# MinieasyMySens-V02-Build008.net
KiCad netlist of a schematic drawn in EAGLE
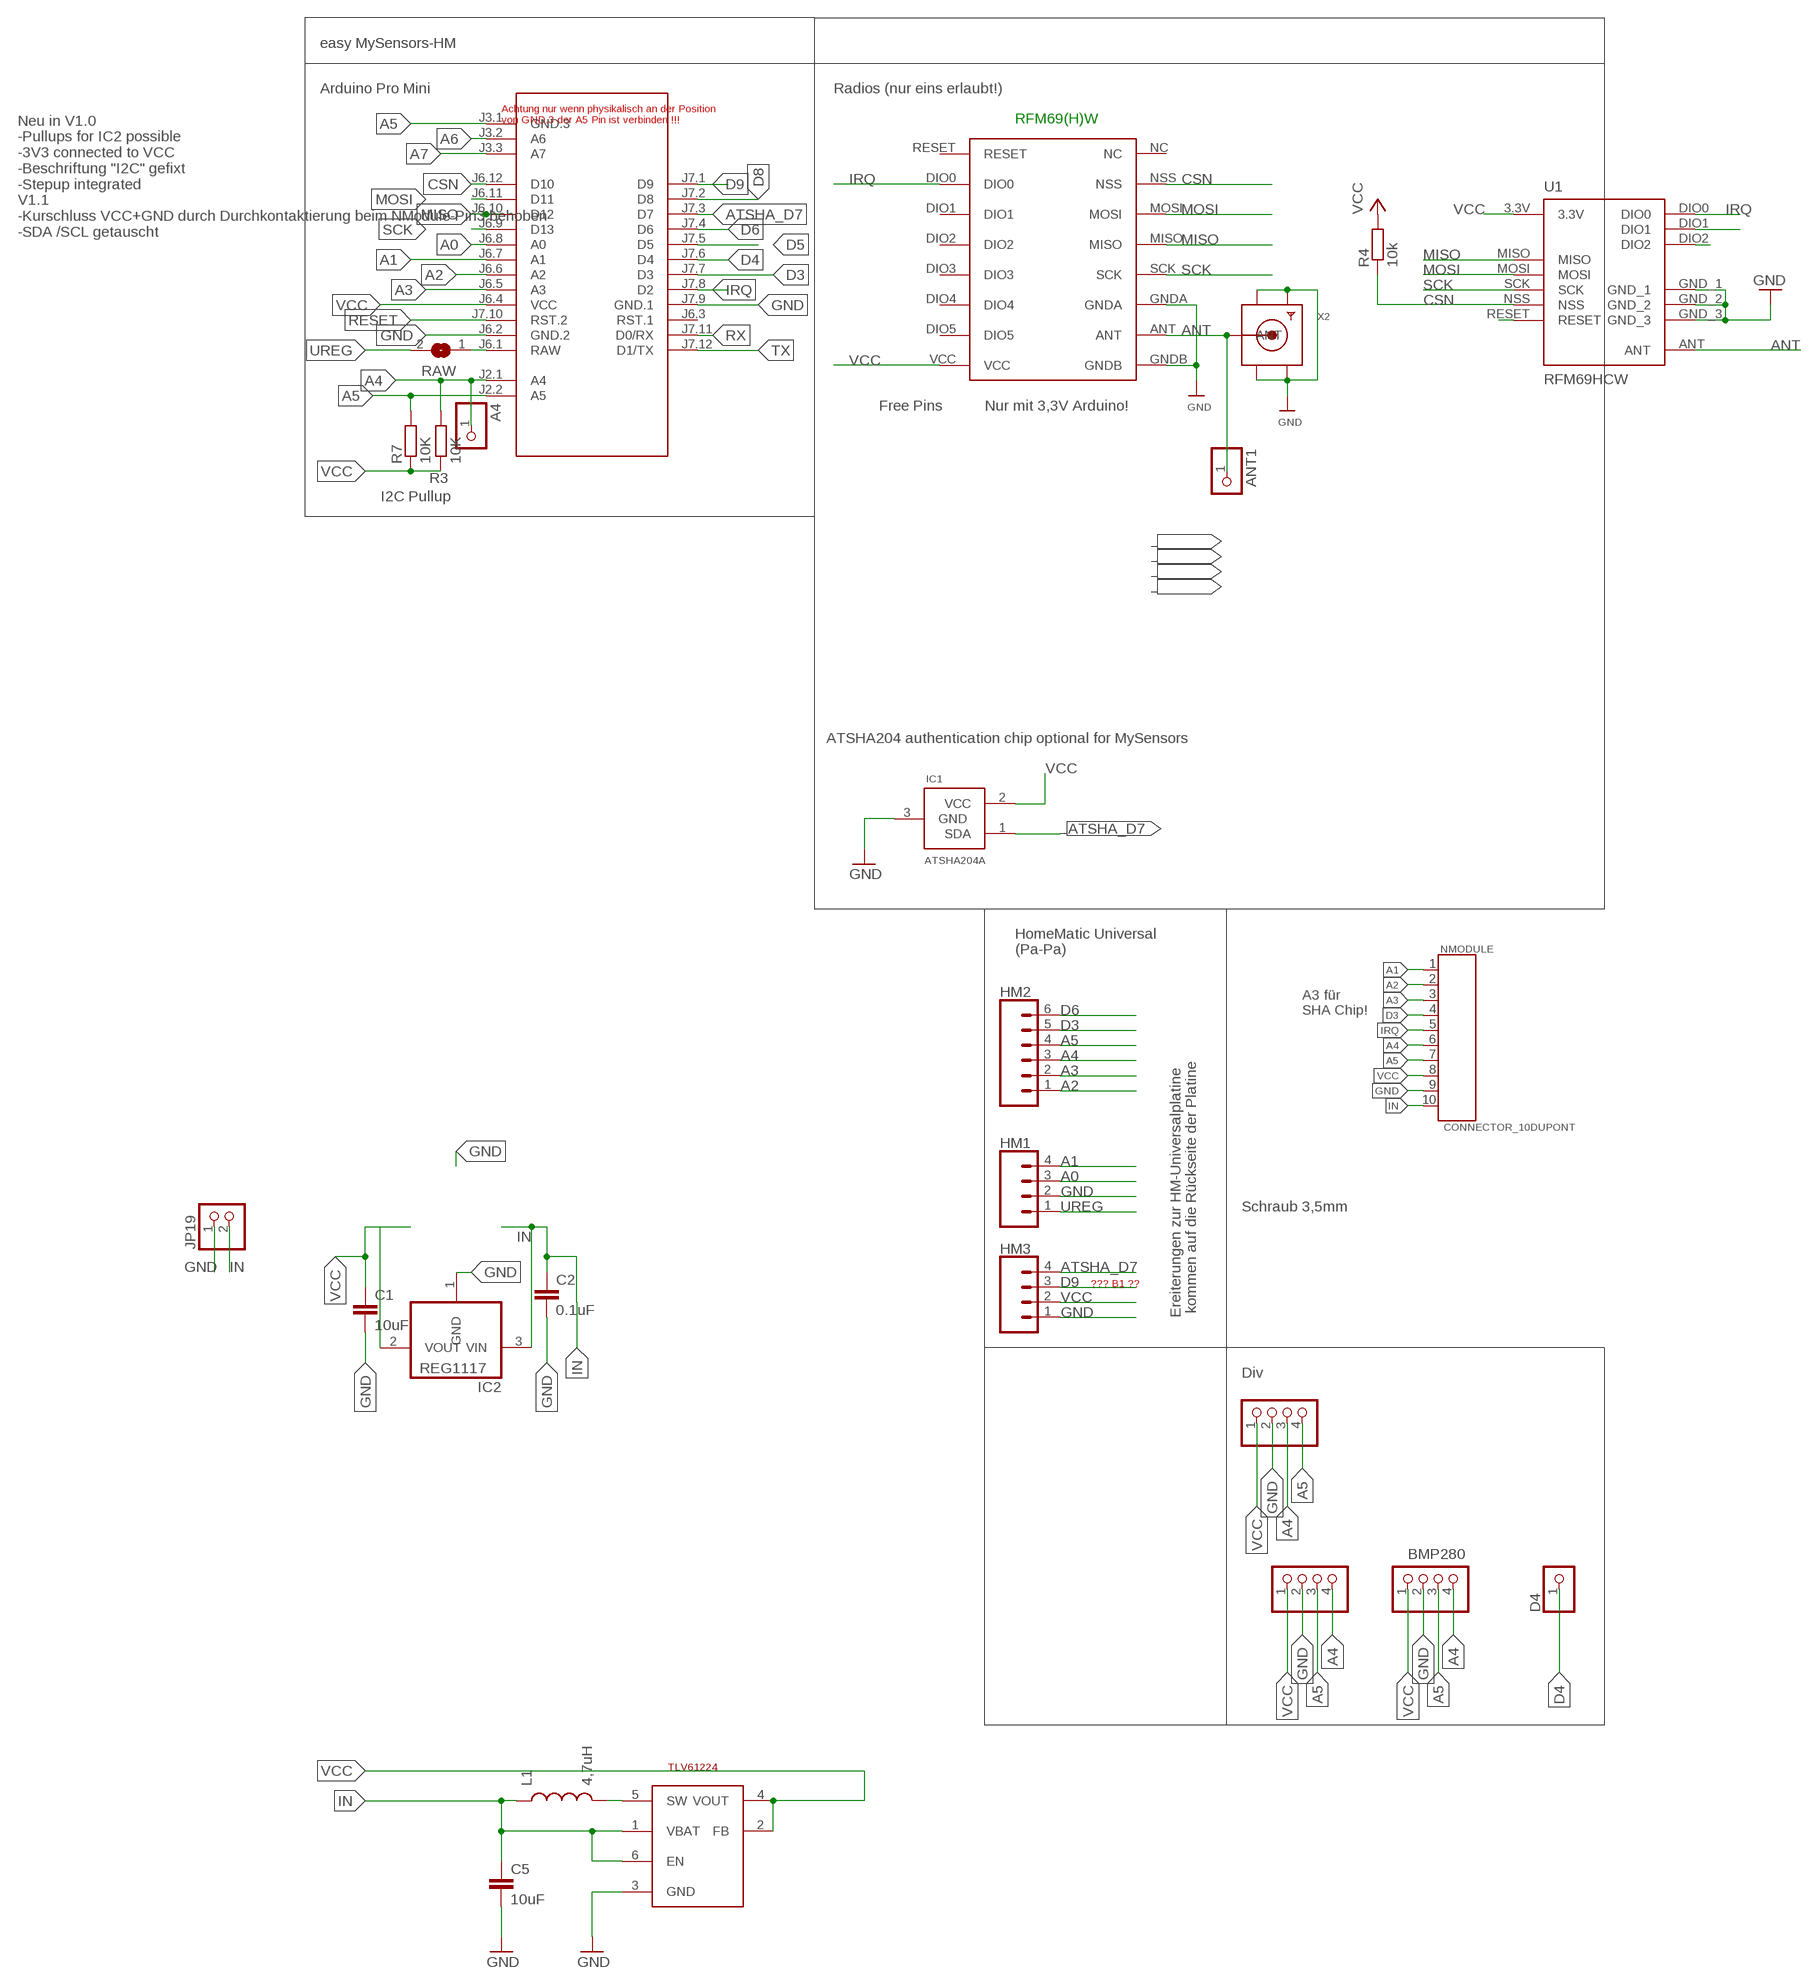
[diagram p0: schematic, sheet 1]

(export (version "E")
  (design (tool "Eeschema 10.0.6"))
  (components
    (comp (ref "A4")
      (value "PINHD-1X1")
      (footprint "eagle-import:1X01")
      (libsource (lib "eagle-import") (part "PINHD-1X1"))
    )
    (comp (ref "ANT1")
      (value "PINHD-1X1")
      (footprint "eagle-import:1X01")
      (libsource (lib "eagle-import") (part "PINHD-1X1"))
    )
    (comp (ref "BH1750")
      (value "PINHD-1X04_2.54-S")
      (footprint "eagle-import:1X04-S")
      (libsource (lib "eagle-import") (part "PINHD-1X04_2.54-S"))
    )
    (comp (ref "C1")
      (value "10uF")
      (footprint "eagle-import:C1210")
      (libsource (lib "eagle-import") (part "C-EUC1210"))
    )
    (comp (ref "C2")
      (value "0.1uF")
      (footprint "eagle-import:C1206")
      (libsource (lib "eagle-import") (part "C-EUC1206"))
    )
    (comp (ref "C5")
      (value "10uF")
      (footprint "eagle-import:0805")
      (libsource (lib "eagle-import") (part "CAP0805"))
    )
    (comp (ref "D4")
      (value "PINHD-1X1")
      (footprint "eagle-import:1X01")
      (libsource (lib "eagle-import") (part "PINHD-1X1"))
    )
    (comp (ref "HM1")
      (value "CONN_04")
      (footprint "eagle-import:1X04")
      (libsource (lib "eagle-import") (part "CONN_04"))
    )
    (comp (ref "HM2")
      (value "CONN_06SILK_FEMALE_PTH")
      (footprint "eagle-import:1X06")
      (libsource (lib "eagle-import") (part "CONN_06SILK_FEMALE_PTH"))
    )
    (comp (ref "HM3")
      (value "CONN_04")
      (footprint "eagle-import:1X04")
      (libsource (lib "eagle-import") (part "CONN_04"))
    )
    (comp (ref "I2C-1")
      (value "PINHD-1X04_2.54-S")
      (footprint "eagle-import:1X04-S")
      (libsource (lib "eagle-import") (part "PINHD-1X04_2.54-S"))
    )
    (comp (ref "I2C-2")
      (value "PINHD-1X04_2.54-S")
      (footprint "eagle-import:1X04-S")
      (libsource (lib "eagle-import") (part "PINHD-1X04_2.54-S"))
    )
    (comp (ref "IC1")
      (value "ATSHA204A")
      (footprint "eagle-import:SOT23")
      (libsource (lib "eagle-import") (part "ATSHA204A"))
    )
    (comp (ref "IC2")
      (value "REG1117")
      (footprint "eagle-import:SOT223")
      (libsource (lib "eagle-import") (part "REG1117"))
    )
    (comp (ref "JP19")
      (value "PINHD-1X2")
      (footprint "eagle-import:1X02")
      (libsource (lib "eagle-import") (part "PINHD-1X2"))
    )
    (comp (ref "L1")
      (value "4,7uH")
      (footprint "eagle-import:0805")
      (libsource (lib "eagle-import") (part "INDUCTOR0805"))
    )
    (comp (ref "M1")
      (value "ARDUINO-PRO-MINI-3.3V#NP")
      (footprint "eagle-import:ARDUINO-PRO-MINI#NP")
      (libsource (lib "eagle-import") (part "ARDUINO-PRO-MINI-#NP3.3V"))
    )
    (comp (ref "NMODULE")
      (value "CONNECTOR_10DUPONT")
      (footprint "eagle-import:DUPONT_10")
      (libsource (lib "eagle-import") (part "CONNECTOR_10DUPONT"))
    )
    (comp (ref "R3")
      (value "10K")
      (footprint "eagle-import:R0805")
      (libsource (lib "eagle-import") (part "R-EU_R0805"))
    )
    (comp (ref "R4")
      (value "10k")
      (footprint "eagle-import:M0805")
      (libsource (lib "eagle-import") (part "R-EU_M0805"))
    )
    (comp (ref "R7")
      (value "10K")
      (footprint "eagle-import:R0805")
      (libsource (lib "eagle-import") (part "R-EU_R0805"))
    )
    (comp (ref "RAW") (value "SJ") (footprint "eagle-import:SJ") (libsource (lib "eagle-import") (part "SJ")))
    (comp (ref "RFM69W")
      (value "RFM69HW")
      (footprint "eagle-import:RFM")
      (libsource (lib "eagle-import") (part "RFM69HW"))
    )
    (comp (ref "STEPUP")
      (value "TLV61224")
      (footprint "eagle-import:SOT23-6L")
      (libsource (lib "eagle-import") (part "TI-TLV61224"))
    )
    (comp (ref "U1")
      (value "RFM69HCW")
      (footprint "eagle-import:RFM69HCW-XXXS2")
      (libsource (lib "eagle-import") (part "RFM69HCW"))
    )
    (comp (ref "X2")
      (value "SMACONNECTOR_EDGE")
      (footprint "eagle-import:SMA_EDGELAUNCH")
      (libsource (lib "eagle-import") (part "SMACONNECTOR_EDGE"))
    )
  )
  (nets
    (net (code "1") (name "/ANT") (class "Default")
      (node (ref "ANT1") (pin "1") (pinfunction "1_1") (pintype "passive"))
      (node (ref "RFM69W") (pin "ANT") (pinfunction "ANT_ANT") (pintype "bidirectional"))
      (node (ref "U1") (pin "ANT") (pinfunction "ANT_ANT") (pintype "passive"))
      (node (ref "X2") (pin "P") (pinfunction "ANT_P") (pintype "bidirectional"))
    )
    (net (code "2") (name "A0") (class "Default")
      (node (ref "HM1") (pin "3") (pinfunction "3_3") (pintype "passive"))
      (node (ref "M1") (pin "J6.8") (pinfunction "A0_J6.8") (pintype "bidirectional"))
    )
    (net (code "3") (name "A1") (class "Default")
      (node (ref "HM1") (pin "4") (pinfunction "4_4") (pintype "passive"))
      (node (ref "M1") (pin "J6.7") (pinfunction "A1_J6.7") (pintype "bidirectional"))
      (node (ref "NMODULE") (pin "1") (pinfunction "1_1") (pintype "bidirectional"))
    )
    (net (code "4") (name "A2") (class "Default")
      (node (ref "HM2") (pin "1") (pinfunction "1_1") (pintype "passive"))
      (node (ref "M1") (pin "J6.6") (pinfunction "A2_J6.6") (pintype "bidirectional"))
      (node (ref "NMODULE") (pin "2") (pinfunction "2_2") (pintype "bidirectional"))
    )
    (net (code "5") (name "A3") (class "Default")
      (node (ref "HM2") (pin "2") (pinfunction "2_2") (pintype "passive"))
      (node (ref "M1") (pin "J6.5") (pinfunction "A3_J6.5") (pintype "bidirectional"))
      (node (ref "NMODULE") (pin "3") (pinfunction "3_3") (pintype "bidirectional"))
    )
    (net (code "6") (name "A4") (class "Default")
      (node (ref "A4") (pin "1") (pinfunction "1_1") (pintype "passive"))
      (node (ref "BH1750") (pin "4") (pinfunction "4_4") (pintype "passive"))
      (node (ref "HM2") (pin "3") (pinfunction "3_3") (pintype "passive"))
      (node (ref "I2C-1") (pin "4") (pinfunction "4_4") (pintype "passive"))
      (node (ref "I2C-2") (pin "3") (pinfunction "3_3") (pintype "passive"))
      (node (ref "M1") (pin "J2.1") (pinfunction "A4_J2.1") (pintype "bidirectional"))
      (node (ref "NMODULE") (pin "6") (pinfunction "6_6") (pintype "bidirectional"))
      (node (ref "R3") (pin "2") (pinfunction "2_2") (pintype "passive"))
    )
    (net (code "7") (name "A5") (class "Default")
      (node (ref "BH1750") (pin "3") (pinfunction "3_3") (pintype "passive"))
      (node (ref "HM2") (pin "4") (pinfunction "4_4") (pintype "passive"))
      (node (ref "I2C-1") (pin "3") (pinfunction "3_3") (pintype "passive"))
      (node (ref "I2C-2") (pin "4") (pinfunction "4_4") (pintype "passive"))
      (node (ref "M1") (pin "J2.2") (pinfunction "A5_J2.2") (pintype "bidirectional"))
      (node (ref "M1") (pin "J3.1") (pinfunction "GND.3_J3.1") (pintype "bidirectional"))
      (node (ref "NMODULE") (pin "7") (pinfunction "7_7") (pintype "bidirectional"))
      (node (ref "R7") (pin "2") (pinfunction "2_2") (pintype "passive"))
    )
    (net (code "8") (name "A6") (class "Default")
      (node (ref "M1") (pin "J3.2") (pinfunction "A6_J3.2") (pintype "bidirectional"))
    )
    (net (code "9") (name "A7") (class "Default")
      (node (ref "M1") (pin "J3.3") (pinfunction "A7_J3.3") (pintype "bidirectional"))
    )
    (net (code "10") (name "ATSHA_D7") (class "Default")
      (node (ref "HM3") (pin "4") (pinfunction "4_4") (pintype "passive"))
      (node (ref "IC1") (pin "1") (pinfunction "SDA_1") (pintype "bidirectional"))
      (node (ref "M1") (pin "J7.3") (pinfunction "D7_J7.3") (pintype "bidirectional"))
    )
    (net (code "11") (name "CSN") (class "Default")
      (node (ref "M1") (pin "J6.12") (pinfunction "D10_J6.12") (pintype "bidirectional"))
      (node (ref "R4") (pin "1") (pinfunction "1_1") (pintype "passive"))
      (node (ref "RFM69W") (pin "NSS") (pinfunction "NSS_NSS") (pintype "bidirectional"))
      (node (ref "U1") (pin "NSS") (pinfunction "NSS_NSS") (pintype "input"))
    )
    (net (code "12") (name "D3") (class "Default")
      (node (ref "HM2") (pin "5") (pinfunction "5_5") (pintype "passive"))
      (node (ref "M1") (pin "J7.7") (pinfunction "D3_J7.7") (pintype "bidirectional"))
      (node (ref "NMODULE") (pin "4") (pinfunction "4_4") (pintype "bidirectional"))
    )
    (net (code "13") (name "D4") (class "Default")
      (node (ref "D4") (pin "1") (pinfunction "1_1") (pintype "passive"))
      (node (ref "M1") (pin "J7.6") (pinfunction "D4_J7.6") (pintype "bidirectional"))
    )
    (net (code "14") (name "D5") (class "Default")
      (node (ref "M1") (pin "J7.5") (pinfunction "D5_J7.5") (pintype "bidirectional"))
    )
    (net (code "15") (name "D6") (class "Default")
      (node (ref "HM2") (pin "6") (pinfunction "6_6") (pintype "passive"))
      (node (ref "M1") (pin "J7.4") (pinfunction "D6_J7.4") (pintype "bidirectional"))
    )
    (net (code "16") (name "D8") (class "Default")
      (node (ref "M1") (pin "J7.2") (pinfunction "D8_J7.2") (pintype "bidirectional"))
    )
    (net (code "17") (name "D9") (class "Default")
      (node (ref "HM3") (pin "3") (pinfunction "3_3") (pintype "passive"))
      (node (ref "M1") (pin "J7.1") (pinfunction "D9_J7.1") (pintype "bidirectional"))
    )
    (net (code "18") (name "GND") (class "Default")
      (node (ref "BH1750") (pin "2") (pinfunction "2_2") (pintype "passive"))
      (node (ref "C1") (pin "2") (pinfunction "2_2") (pintype "passive"))
      (node (ref "C2") (pin "2") (pinfunction "2_2") (pintype "passive"))
      (node (ref "C5") (pin "2") (pinfunction "2_2") (pintype "passive"))
      (node (ref "HM1") (pin "2") (pinfunction "2_2") (pintype "passive"))
      (node (ref "HM3") (pin "1") (pinfunction "1_1") (pintype "passive"))
      (node (ref "I2C-1") (pin "2") (pinfunction "2_2") (pintype "passive"))
      (node (ref "I2C-2") (pin "2") (pinfunction "2_2") (pintype "passive"))
      (node (ref "IC1") (pin "3") (pinfunction "GND_3") (pintype "bidirectional"))
      (node (ref "IC2") (pin "1") (pinfunction "GND_1") (pintype "power_in"))
      (node (ref "JP19") (pin "1") (pinfunction "1_1") (pintype "passive"))
      (node (ref "M1") (pin "J6.2") (pinfunction "GND.2_J6.2") (pintype "power_in"))
      (node (ref "M1") (pin "J7.9") (pinfunction "GND.1_J7.9") (pintype "power_in"))
      (node (ref "NMODULE") (pin "9") (pinfunction "9_9") (pintype "bidirectional"))
      (node (ref "RFM69W") (pin "GNDA") (pinfunction "GNDA_GNDA") (pintype "bidirectional"))
      (node (ref "RFM69W") (pin "GNDB") (pinfunction "GNDB_GNDB") (pintype "bidirectional"))
      (node (ref "STEPUP") (pin "3") (pinfunction "GND_3") (pintype "power_in"))
      (node (ref "U1") (pin "GND_1") (pinfunction "GND_1_GND_1") (pintype "power_in"))
      (node (ref "U1") (pin "GND_2") (pinfunction "GND_2_GND_2") (pintype "power_in"))
      (node (ref "U1") (pin "GND_3") (pinfunction "GND_3_GND_3") (pintype "power_in"))
      (node (ref "X2") (pin "GND@1") (pinfunction "GND4_GND@1") (pintype "power_in"))
      (node (ref "X2") (pin "GND@2") (pinfunction "GND3_GND@2") (pintype "power_in"))
      (node (ref "X2") (pin "GND@3") (pinfunction "GND2_GND@3") (pintype "power_in"))
      (node (ref "X2") (pin "GND@4") (pinfunction "GND1_GND@4") (pintype "power_in"))
    )
    (net (code "19") (name "IN") (class "Default")
      (node (ref "C2") (pin "1") (pinfunction "1_1") (pintype "passive"))
      (node (ref "C5") (pin "1") (pinfunction "1_1") (pintype "passive"))
      (node (ref "IC2") (pin "3") (pinfunction "VIN_3") (pintype "input"))
      (node (ref "JP19") (pin "2") (pinfunction "2_2") (pintype "passive"))
      (node (ref "L1") (pin "1") (pinfunction "1_1") (pintype "passive"))
      (node (ref "NMODULE") (pin "10") (pinfunction "10_10") (pintype "bidirectional"))
      (node (ref "STEPUP") (pin "1") (pinfunction "VBAT_1") (pintype "power_in"))
      (node (ref "STEPUP") (pin "6") (pinfunction "EN_6") (pintype "input"))
    )
    (net (code "20") (name "IRQ") (class "Default")
      (node (ref "M1") (pin "J7.8") (pinfunction "D2_J7.8") (pintype "bidirectional"))
      (node (ref "NMODULE") (pin "5") (pinfunction "5_5") (pintype "bidirectional"))
      (node (ref "RFM69W") (pin "DIO0") (pinfunction "DIO0_DIO0") (pintype "bidirectional"))
      (node (ref "U1") (pin "DIO0") (pinfunction "DIO0_DIO0") (pintype "bidirectional"))
    )
    (net (code "21") (name "MISO") (class "Default")
      (node (ref "M1") (pin "J6.10") (pinfunction "D12_J6.10") (pintype "bidirectional"))
      (node (ref "RFM69W") (pin "MISO") (pinfunction "MISO_MISO") (pintype "bidirectional"))
      (node (ref "U1") (pin "MISO") (pinfunction "MISO_MISO") (pintype "bidirectional"))
    )
    (net (code "22") (name "MOSI") (class "Default")
      (node (ref "M1") (pin "J6.11") (pinfunction "D11_J6.11") (pintype "bidirectional"))
      (node (ref "RFM69W") (pin "MOSI") (pinfunction "MOSI_MOSI") (pintype "bidirectional"))
      (node (ref "U1") (pin "MOSI") (pinfunction "MOSI_MOSI") (pintype "input"))
    )
    (net (code "23") (name "Net-(M1-RAW)") (class "Default")
      (node (ref "M1") (pin "J6.1") (pinfunction "RAW_J6.1") (pintype "power_in"))
      (node (ref "RAW") (pin "1") (pinfunction "1_1") (pintype "passive"))
    )
    (net (code "24") (name "Net-(STEPUP-SW)") (class "Default")
      (node (ref "L1") (pin "2") (pinfunction "2_2") (pintype "passive"))
      (node (ref "STEPUP") (pin "5") (pinfunction "SW_5") (pintype "power_in"))
    )
    (net (code "25") (name "RESET") (class "Default")
      (node (ref "M1") (pin "J7.10") (pinfunction "RST.2_J7.10") (pintype "bidirectional"))
    )
    (net (code "26") (name "RX") (class "Default")
      (node (ref "M1") (pin "J7.11") (pinfunction "D0/RX_J7.11") (pintype "bidirectional"))
    )
    (net (code "27") (name "SCK") (class "Default")
      (node (ref "M1") (pin "J6.9") (pinfunction "D13_J6.9") (pintype "bidirectional"))
      (node (ref "RFM69W") (pin "SCK") (pinfunction "SCK_SCK") (pintype "bidirectional"))
      (node (ref "U1") (pin "SCK") (pinfunction "SCK_SCK") (pintype "input"))
    )
    (net (code "28") (name "TX") (class "Default")
      (node (ref "M1") (pin "J7.12") (pinfunction "D1/TX_J7.12") (pintype "bidirectional"))
    )
    (net (code "29") (name "UREG") (class "Default")
      (node (ref "HM1") (pin "1") (pinfunction "1_1") (pintype "passive"))
      (node (ref "RAW") (pin "2") (pinfunction "2_2") (pintype "passive"))
    )
    (net (code "30") (name "VCC") (class "Default")
      (node (ref "BH1750") (pin "1") (pinfunction "1_1") (pintype "passive"))
      (node (ref "C1") (pin "1") (pinfunction "1_1") (pintype "passive"))
      (node (ref "HM3") (pin "2") (pinfunction "2_2") (pintype "passive"))
      (node (ref "I2C-1") (pin "1") (pinfunction "1_1") (pintype "passive"))
      (node (ref "I2C-2") (pin "1") (pinfunction "1_1") (pintype "passive"))
      (node (ref "IC1") (pin "2") (pinfunction "VCC_2") (pintype "bidirectional"))
      (node (ref "IC2") (pin "2") (pinfunction "VOUT_2") (pintype "output"))
      (node (ref "M1") (pin "J6.4") (pinfunction "VCC_J6.4") (pintype "power_in"))
      (node (ref "NMODULE") (pin "8") (pinfunction "8_8") (pintype "bidirectional"))
      (node (ref "R3") (pin "1") (pinfunction "1_1") (pintype "passive"))
      (node (ref "R4") (pin "2") (pinfunction "2_2") (pintype "passive"))
      (node (ref "R7") (pin "1") (pinfunction "1_1") (pintype "passive"))
      (node (ref "RFM69W") (pin "VCC") (pinfunction "VCC_VCC") (pintype "bidirectional"))
      (node (ref "STEPUP") (pin "2") (pinfunction "FB_2") (pintype "input"))
      (node (ref "STEPUP") (pin "4") (pinfunction "VOUT_4") (pintype "power_in"))
      (node (ref "U1") (pin "3.3V") (pinfunction "3.3V_3.3V") (pintype "power_in"))
    )
    (net (code "31") (name "unconnected-(M1-RST.1-PadJ6.3)") (class "Default")
      (node (ref "M1") (pin "J6.3") (pinfunction "RST.1_J6.3") (pintype "bidirectional"))
    )
    (net (code "32") (name "unconnected-(RFM69W-PadDIO1)") (class "Default")
      (node (ref "RFM69W") (pin "DIO1") (pinfunction "DIO1_DIO1") (pintype "bidirectional"))
    )
    (net (code "33") (name "unconnected-(RFM69W-PadDIO2)") (class "Default")
      (node (ref "RFM69W") (pin "DIO2") (pinfunction "DIO2_DIO2") (pintype "bidirectional"))
    )
    (net (code "34") (name "unconnected-(RFM69W-PadDIO3)") (class "Default")
      (node (ref "RFM69W") (pin "DIO3") (pinfunction "DIO3_DIO3") (pintype "bidirectional"))
    )
    (net (code "35") (name "unconnected-(RFM69W-PadDIO4)") (class "Default")
      (node (ref "RFM69W") (pin "DIO4") (pinfunction "DIO4_DIO4") (pintype "bidirectional"))
    )
    (net (code "36") (name "unconnected-(RFM69W-PadDIO5)") (class "Default")
      (node (ref "RFM69W") (pin "DIO5") (pinfunction "DIO5_DIO5") (pintype "bidirectional"))
    )
    (net (code "37") (name "unconnected-(RFM69W-PadNC)") (class "Default")
      (node (ref "RFM69W") (pin "NC") (pinfunction "NC_NC") (pintype "bidirectional"))
    )
    (net (code "38") (name "unconnected-(RFM69W-PadRESET)") (class "Default")
      (node (ref "RFM69W") (pin "RESET") (pinfunction "RESET_RESET") (pintype "bidirectional"))
    )
    (net (code "39") (name "unconnected-(U1-PadDIO1)") (class "Default")
      (node (ref "U1") (pin "DIO1") (pinfunction "DIO1_DIO1") (pintype "bidirectional"))
    )
    (net (code "40") (name "unconnected-(U1-PadDIO2)") (class "Default")
      (node (ref "U1") (pin "DIO2") (pinfunction "DIO2_DIO2") (pintype "bidirectional"))
    )
    (net (code "41") (name "unconnected-(U1-PadRESET)") (class "Default")
      (node (ref "U1") (pin "RESET") (pinfunction "RESET_RESET") (pintype "input"))
    )
  )
)
